# 11_-BATTERY_BACKUP.net
KiCad netlist of a schematic drawn in Altium Designer
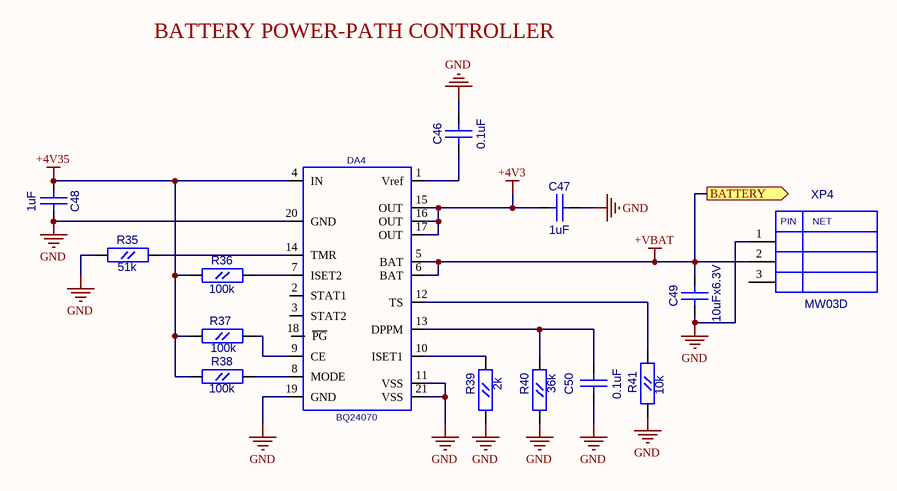
[diagram p0: [11]-BATTERY_BACKUP.SchDoc]

(export (version "E")
  (design (tool "Eeschema 10.0.6"))
  (components
    (comp (ref "C46")
      (value "0.1uF")
      (footprint "CC0603")
      (description "CC0603")
      (libsource (lib "gprs_modem_2") (part "CC0603"))
    )
    (comp (ref "C47")
      (value "1uF")
      (footprint "CC0603")
      (description "CC0603")
      (libsource (lib "gprs_modem_2") (part "CC0603"))
    )
    (comp (ref "C48")
      (value "1uF")
      (footprint "CC0603")
      (description "CC0603")
      (libsource (lib "gprs_modem_2") (part "CC0603"))
    )
    (comp (ref "C49")
      (value "10uFx6.3V")
      (footprint "CC0805")
      (description "CC0805")
      (libsource (lib "gprs_modem_2") (part "CC0805"))
    )
    (comp (ref "C50")
      (value "0.1uF")
      (footprint "CC0603")
      (description "CC0603")
      (libsource (lib "gprs_modem_2") (part "CC0603"))
    )
    (comp (ref "DA4")
      (value "BQ24070")
      (footprint "P-PQFP-N20")
      (libsource (lib "gprs_modem") (part "BQ24070"))
    )
    (comp (ref "R35")
      (value "51k")
      (footprint "RC0603")
      (description "RC0603")
      (libsource (lib "gprs_modem_2") (part "RC0603"))
    )
    (comp (ref "R36")
      (value "100k")
      (footprint "RC0603")
      (description "RC0603")
      (libsource (lib "gprs_modem_2") (part "RC0603"))
    )
    (comp (ref "R37")
      (value "100k")
      (footprint "RC0603")
      (description "RC0603")
      (libsource (lib "gprs_modem_2") (part "RC0603"))
    )
    (comp (ref "R38")
      (value "100k")
      (footprint "RC0603")
      (description "RC0603")
      (libsource (lib "gprs_modem_2") (part "RC0603"))
    )
    (comp (ref "R39")
      (value "2k")
      (footprint "RC0603")
      (description "RC0603")
      (libsource (lib "gprs_modem_2") (part "RC0603"))
    )
    (comp (ref "R40")
      (value "36k")
      (footprint "RC0603")
      (description "RC0603")
      (libsource (lib "gprs_modem_2") (part "RC0603"))
    )
    (comp (ref "R41")
      (value "10k")
      (footprint "RC0603")
      (description "RC0603")
      (libsource (lib "gprs_modem_2") (part "RC0603"))
    )
    (comp (ref "XP4") (value "MW03D") (footprint "MW03D") (libsource (lib "gprs_modem") (part "MW03D")))
  )
  (nets
    (net (code "1") (name "+4V3") (class "Default")
      (node (ref "C47") (pin "1") (pinfunction "A_1") (pintype "passive"))
      (node (ref "DA4") (pin "15") (pinfunction "OUT_15") (pintype "passive"))
      (node (ref "DA4") (pin "16") (pinfunction "OUT_16") (pintype "passive"))
      (node (ref "DA4") (pin "17") (pinfunction "OUT_17") (pintype "passive"))
    )
    (net (code "2") (name "+4V35") (class "Default")
      (node (ref "C48") (pin "1") (pinfunction "A_1") (pintype "passive"))
      (node (ref "DA4") (pin "4") (pinfunction "IN_4") (pintype "passive"))
      (node (ref "R36") (pin "2") (pinfunction "B_2") (pintype "passive"))
      (node (ref "R37") (pin "2") (pinfunction "B_2") (pintype "passive"))
      (node (ref "R38") (pin "2") (pinfunction "B_2") (pintype "passive"))
    )
    (net (code "3") (name "+VBAT") (class "Default")
      (node (ref "C49") (pin "2") (pinfunction "B_2") (pintype "passive"))
      (node (ref "DA4") (pin "5") (pinfunction "BAT_5") (pintype "passive"))
      (node (ref "DA4") (pin "6") (pinfunction "BAT_6") (pintype "passive"))
      (node (ref "XP4") (pin "2") (pinfunction "2_2") (pintype "passive"))
    )
    (net (code "4") (name "GND") (class "Default")
      (node (ref "C46") (pin "2") (pinfunction "B_2") (pintype "passive"))
      (node (ref "C47") (pin "2") (pinfunction "B_2") (pintype "passive"))
      (node (ref "C48") (pin "2") (pinfunction "B_2") (pintype "passive"))
      (node (ref "C49") (pin "1") (pinfunction "A_1") (pintype "passive"))
      (node (ref "C50") (pin "2") (pinfunction "B_2") (pintype "passive"))
      (node (ref "DA4") (pin "11") (pinfunction "VSS_11") (pintype "passive"))
      (node (ref "DA4") (pin "19") (pinfunction "GND_19") (pintype "passive"))
      (node (ref "DA4") (pin "20") (pinfunction "GND_20") (pintype "passive"))
      (node (ref "DA4") (pin "21") (pinfunction "VSS_21") (pintype "passive"))
      (node (ref "R35") (pin "2") (pinfunction "B_2") (pintype "passive"))
      (node (ref "R39") (pin "2") (pinfunction "B_2") (pintype "passive"))
      (node (ref "R40") (pin "2") (pinfunction "B_2") (pintype "passive"))
      (node (ref "R41") (pin "2") (pinfunction "B_2") (pintype "passive"))
      (node (ref "XP4") (pin "1") (pinfunction "1_1") (pintype "passive"))
    )
    (net (code "5") (name "Net-(C46-A)") (class "Default")
      (node (ref "C46") (pin "1") (pinfunction "A_1") (pintype "passive"))
      (node (ref "DA4") (pin "1") (pinfunction "Vref_1") (pintype "passive"))
    )
    (net (code "6") (name "Net-(C50-A)") (class "Default")
      (node (ref "C50") (pin "1") (pinfunction "A_1") (pintype "passive"))
      (node (ref "DA4") (pin "13") (pinfunction "DPPM_13") (pintype "passive"))
      (node (ref "R40") (pin "1") (pinfunction "A_1") (pintype "passive"))
    )
    (net (code "7") (name "Net-(DA4-CE)") (class "Default")
      (node (ref "DA4") (pin "9") (pinfunction "CE_9") (pintype "passive"))
      (node (ref "R37") (pin "1") (pinfunction "A_1") (pintype "passive"))
    )
    (net (code "8") (name "Net-(DA4-ISET1)") (class "Default")
      (node (ref "DA4") (pin "10") (pinfunction "ISET1_10") (pintype "passive"))
      (node (ref "R39") (pin "1") (pinfunction "A_1") (pintype "passive"))
    )
    (net (code "9") (name "Net-(DA4-ISET2)") (class "Default")
      (node (ref "DA4") (pin "7") (pinfunction "ISET2_7") (pintype "passive"))
      (node (ref "R36") (pin "1") (pinfunction "A_1") (pintype "passive"))
    )
    (net (code "10") (name "Net-(DA4-MODE)") (class "Default")
      (node (ref "DA4") (pin "8") (pinfunction "MODE_8") (pintype "passive"))
      (node (ref "R38") (pin "1") (pinfunction "A_1") (pintype "passive"))
    )
    (net (code "11") (name "Net-(DA4-TMR)") (class "Default")
      (node (ref "DA4") (pin "14") (pinfunction "TMR_14") (pintype "passive"))
      (node (ref "R35") (pin "1") (pinfunction "A_1") (pintype "passive"))
    )
    (net (code "12") (name "Net-(DA4-TS)") (class "Default")
      (node (ref "DA4") (pin "12") (pinfunction "TS_12") (pintype "passive"))
      (node (ref "R41") (pin "1") (pinfunction "A_1") (pintype "passive"))
    )
    (net (code "13") (name "unconnected-(DA4-STAT1-Pad2)") (class "Default")
      (node (ref "DA4") (pin "2") (pinfunction "STAT1_2") (pintype "passive"))
    )
    (net (code "14") (name "unconnected-(DA4-STAT2-Pad3)") (class "Default")
      (node (ref "DA4") (pin "3") (pinfunction "STAT2_3") (pintype "passive"))
    )
    (net (code "15") (name "unconnected-(DA4-~{PG}-Pad18)") (class "Default")
      (node (ref "DA4") (pin "18") (pinfunction "~{PG}_18") (pintype "passive"))
    )
    (net (code "16") (name "unconnected-(XP4-Pad3)") (class "Default")
      (node (ref "XP4") (pin "3") (pinfunction "3_3") (pintype "passive"))
    )
  )
)
